# LEDs.net
KiCad netlist of a schematic drawn in Altium Designer
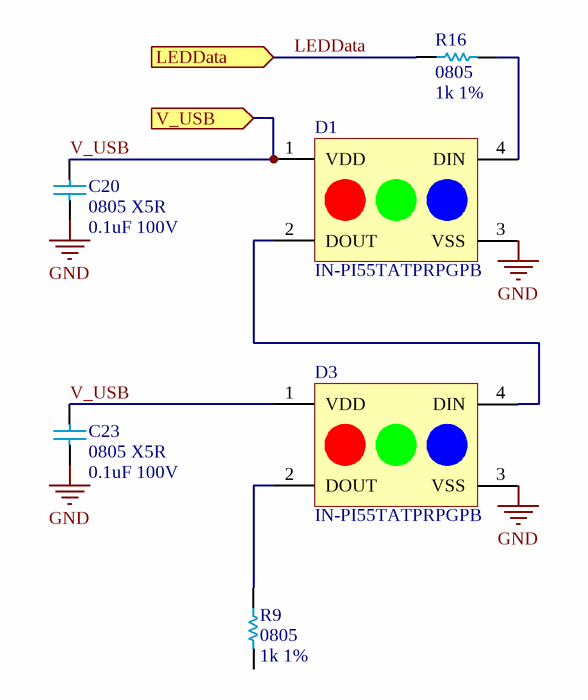
[diagram p0: LEDs.SchDoc]

(export (version "E")
  (design (tool "Eeschema 10.0.6"))
  (components
    (comp (ref "C20")
      (value "0805 X5R")
      (footprint "0805 - TALL")
      (description "0805, X5R or better")
      (fields (field (name "ALTIUM_VALUE") "0.1uF 100V"))
      (libsource (lib "Chip_Passives") (part "Cap 0.1uF 100V"))
    )
    (comp (ref "C23")
      (value "0805 X5R")
      (footprint "0805 - TALL")
      (description "0805, X5R or better")
      (fields (field (name "ALTIUM_VALUE") "0.1uF 100V"))
      (libsource (lib "Chip_Passives") (part "Cap 0.1uF 100V"))
    )
    (comp (ref "D1")
      (value "IN-PI55TATPRPGPB")
      (footprint "IN-PI55TATPRPGPB")
      (description "ADDRESS LED DISCRETE SERIAL RGB")
      (libsource (lib "LEDs") (part "IN-PI55TATPRPGPB"))
    )
    (comp (ref "D3")
      (value "IN-PI55TATPRPGPB")
      (footprint "IN-PI55TATPRPGPB")
      (description "ADDRESS LED DISCRETE SERIAL RGB")
      (libsource (lib "LEDs") (part "IN-PI55TATPRPGPB"))
    )
    (comp (ref "R9")
      (value "0805")
      (footprint "0805")
      (description "Chip resistor, 1/8W 100PPM")
      (fields (field (name "ALTIUM_VALUE") "1k 1%"))
      (libsource (lib "Chip_Passives") (part "Res 1k 1% 0805"))
    )
    (comp (ref "R16")
      (value "0805")
      (footprint "0805")
      (description "Chip resistor, 1/8W 100PPM")
      (fields (field (name "ALTIUM_VALUE") "1k 1%"))
      (libsource (lib "Chip_Passives") (part "Res 1k 1% 0805"))
    )
  )
  (nets
    (net (code "1") (name "/LEDData") (class "Default")
      (node (ref "R16") (pin "2") (pinfunction "2_2") (pintype "passive"))
    )
    (net (code "2") (name "/V_USB") (class "Default")
      (node (ref "C20") (pin "2") (pinfunction "2_2") (pintype "passive"))
      (node (ref "C23") (pin "2") (pinfunction "2_2") (pintype "passive"))
      (node (ref "D1") (pin "1") (pinfunction "VDD_1") (pintype "passive"))
      (node (ref "D3") (pin "1") (pinfunction "VDD_1") (pintype "passive"))
    )
    (net (code "3") (name "GND") (class "Default")
      (node (ref "C20") (pin "1") (pinfunction "1_1") (pintype "passive"))
      (node (ref "C23") (pin "1") (pinfunction "1_1") (pintype "passive"))
      (node (ref "D1") (pin "3") (pinfunction "VSS_3") (pintype "passive"))
      (node (ref "D3") (pin "3") (pinfunction "VSS_3") (pintype "passive"))
    )
    (net (code "4") (name "Net-(D1-DIN)") (class "Default")
      (node (ref "D1") (pin "4") (pinfunction "DIN_4") (pintype "passive"))
      (node (ref "R16") (pin "1") (pinfunction "1_1") (pintype "passive"))
    )
    (net (code "5") (name "Net-(D1-DOUT)") (class "Default")
      (node (ref "D1") (pin "2") (pinfunction "DOUT_2") (pintype "passive"))
      (node (ref "D3") (pin "4") (pinfunction "DIN_4") (pintype "passive"))
    )
    (net (code "6") (name "Net-(D3-DOUT)") (class "Default")
      (node (ref "D3") (pin "2") (pinfunction "DOUT_2") (pintype "passive"))
      (node (ref "R9") (pin "2") (pinfunction "2_2") (pintype "passive"))
    )
    (net (code "7") (name "unconnected-(R9-Pad1)") (class "Default")
      (node (ref "R9") (pin "1") (pinfunction "1_1") (pintype "passive"))
    )
  )
)
